# Potencia.net
KiCad netlist of a schematic drawn in Altium Designer
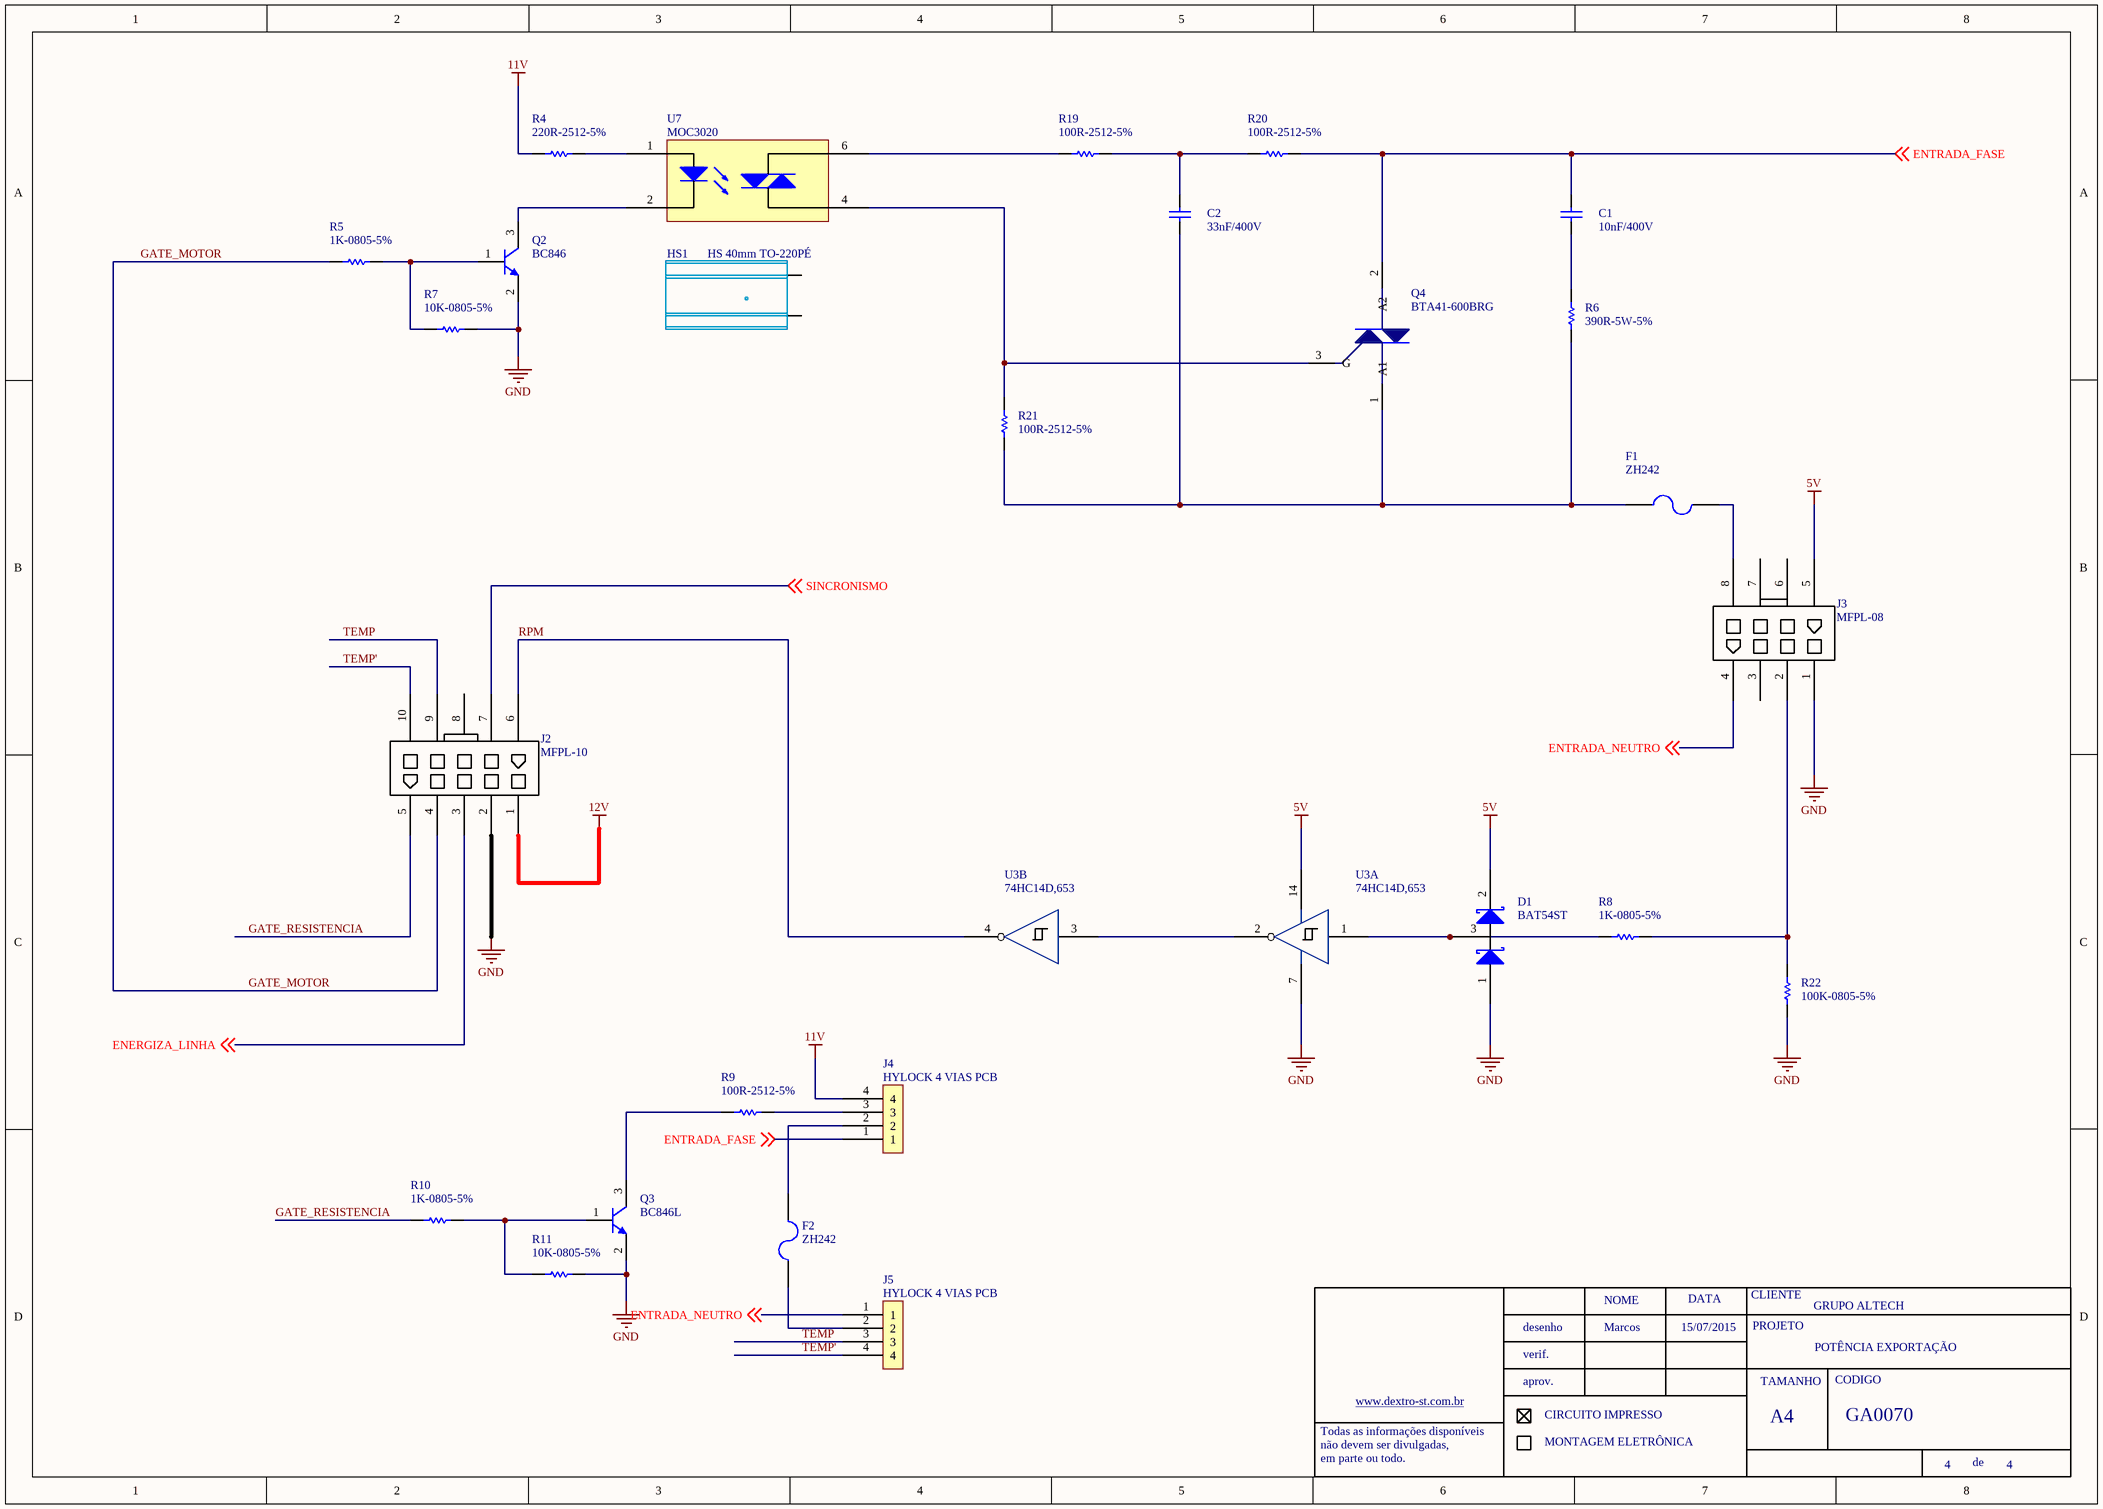
[diagram p0: Potencia.SchDoc]

(export (version "E")
  (design (tool "Eeschema 10.0.6"))
  (components
    (comp (ref "C1")
      (value "10nF/400V")
      (footprint "cap 330nF/250V")
      (description "100nF/50-0805-NPO")
      (libsource (lib "AquinoLib") (part "100nF/50-0805-NPO"))
    )
    (comp (ref "C2")
      (value "33nF/400V")
      (footprint "cap 330nF/250V")
      (description "100nF/50-0805-NPO")
      (libsource (lib "AquinoLib") (part "100nF/50-0805-NPO"))
    )
    (comp (ref "D1")
      (value "BAT54ST")
      (footprint "SOT23 - REVISADO ONDA")
      (libsource (lib "AquinoLib") (part "BAT54ST"))
    )
    (comp (ref "F1")
      (value "ZH242")
      (footprint "ZH242_REVISADO")
      (description "PORTA FUSÍVEL TIPO BERÇO")
      (libsource (lib "ChaveDigital3") (part "PORTA FUSÍVEL TIPO BERÇO"))
    )
    (comp (ref "F2")
      (value "ZH242")
      (footprint "ZH242_REVISADO")
      (description "PORTA FUSÍVEL TIPO BERÇO")
      (libsource (lib "ChaveDigital3") (part "PORTA FUSÍVEL TIPO BERÇO"))
    )
    (comp (ref "HS1")
      (value "HS 40mm TO-220PÉ")
      (footprint "dissipador grande")
      (libsource (lib "ChaveDigital3") (part "DISSIPADOR 40mm PÉ"))
    )
    (comp (ref "J2") (value "MFPL-10") (footprint "MFPC-10") (libsource (lib "AquinoLib") (part "MFPL-10")))
    (comp (ref "J3") (value "MFPL-08") (footprint "MFPC-08") (libsource (lib "AquinoLib") (part "MFPL-08")))
    (comp (ref "J4")
      (value "HYLOCK 4 VIAS PCB")
      (footprint "CONECTOR HYLOK 4 VIAS")
      (description "PCMC2-4")
      (libsource (lib "") (part "PCMC2-4_1"))
    )
    (comp (ref "J5")
      (value "HYLOCK 4 VIAS PCB")
      (footprint "CONECTOR HYLOK 4 VIAS")
      (description "PCMC2-4")
      (libsource (lib "AquinoLib") (part "PCMC2-4"))
    )
    (comp (ref "Q2")
      (value "BC846")
      (footprint "SOT23 - REVISADO ONDA")
      (description "BC846L")
      (libsource (lib "AquinoLib") (part "BC846"))
    )
    (comp (ref "Q3") (value "BC846L") (libsource (lib "AquinoLib") (part "BC846")))
    (comp (ref "Q4")
      (value "BTA41-600BRG")
      (footprint "TO-247 - duplicate")
      (libsource (lib "AquinoLib") (part "BTA41-600BRG"))
    )
    (comp (ref "R4")
      (value "220R-2512-5%")
      (footprint "2512 - REVISADO ONDA")
      (libsource (lib "AquinoLib") (part "220R-2512-5%"))
    )
    (comp (ref "R5")
      (value "1K-0805-5%")
      (footprint "0805-REVISADO ONDA")
      (description "10K-0805-5%")
      (libsource (lib "AquinoLib") (part "10K-0805-5%"))
    )
    (comp (ref "R6")
      (value "390R-5W-5%")
      (footprint "RESISTOR 5W FIO")
      (description "47R-5W-5%")
      (libsource (lib "AquinoLib") (part "47R-5W-5%"))
    )
    (comp (ref "R7")
      (value "10K-0805-5%")
      (footprint "0805-REVISADO ONDA")
      (libsource (lib "AquinoLib") (part "10K-0805-5%"))
    )
    (comp (ref "R8")
      (value "1K-0805-5%")
      (footprint "0805-REVISADO ONDA")
      (libsource (lib "AquinoLib") (part "1K-0805-5%"))
    )
    (comp (ref "R9")
      (value "100R-2512-5%")
      (footprint "2512 - REVISADO ONDA")
      (description "100R-0805-5%")
      (libsource (lib "AquinoLib") (part "100R-0805-5%"))
    )
    (comp (ref "R10")
      (value "1K-0805-5%")
      (footprint "0805-REVISADO ONDA")
      (libsource (lib "AquinoLib") (part "1K-0805-5%"))
    )
    (comp (ref "R11")
      (value "10K-0805-5%")
      (footprint "0805-REVISADO ONDA")
      (libsource (lib "AquinoLib") (part "10K-0805-5%"))
    )
    (comp (ref "R19")
      (value "100R-2512-5%")
      (footprint "2512 - REVISADO ONDA")
      (description "220R-2512-5%")
      (libsource (lib "AquinoLib") (part "220R-2512-5%"))
    )
    (comp (ref "R20")
      (value "100R-2512-5%")
      (footprint "2512 - REVISADO ONDA")
      (description "220R-2512-5%")
      (libsource (lib "AquinoLib") (part "220R-2512-5%"))
    )
    (comp (ref "R21")
      (value "100R-2512-5%")
      (footprint "2512 - REVISADO ONDA")
      (description "220R-2512-5%")
      (libsource (lib "AquinoLib") (part "220R-2512-5%"))
    )
    (comp (ref "R22")
      (value "100K-0805-5%")
      (footprint "0805-REVISADO ONDA")
      (libsource (lib "AquinoLib") (part "100K-0805-5%"))
    )
    (comp (ref "U3")
      (value "74HC14D,653")
      (footprint "SOIC 14 PINOS")
      (description "74HC14D")
      (libsource (lib "AquinoLib") (part "74HC14D"))
    )
    (comp (ref "U7") (value "MOC3020") (footprint "dip6") (libsource (lib "AquinoLib") (part "MOC3020")))
  )
  (nets
    (net (code "1") (name "/GATE_MOTOR") (class "Default")
      (node (ref "J2") (pin "4") (pinfunction "4_4") (pintype "passive"))
      (node (ref "R5") (pin "1") (pinfunction "1_1") (pintype "passive"))
    )
    (net (code "2") (name "/GATE_RESISTENCIA") (class "Default")
      (node (ref "J2") (pin "5") (pinfunction "5_5") (pintype "passive"))
      (node (ref "R10") (pin "1") (pinfunction "1_1") (pintype "passive"))
    )
    (net (code "3") (name "/RPM") (class "Default")
      (node (ref "J2") (pin "6") (pinfunction "6_6") (pintype "passive"))
      (node (ref "U3") (pin "4") (pinfunction "4_4") (pintype "passive"))
    )
    (net (code "4") (name "/TEMP") (class "Default")
      (node (ref "J2") (pin "9") (pinfunction "9_9") (pintype "passive"))
      (node (ref "J5") (pin "3") (pinfunction "3_3") (pintype "passive"))
    )
    (net (code "5") (name "/TEMP'") (class "Default")
      (node (ref "J2") (pin "10") (pinfunction "10_10") (pintype "passive"))
      (node (ref "J5") (pin "4") (pinfunction "4_4") (pintype "passive"))
    )
    (net (code "6") (name "5V") (class "Default")
      (node (ref "D1") (pin "2") (pinfunction "2_2") (pintype "passive"))
      (node (ref "J3") (pin "5") (pinfunction "5_5") (pintype "passive"))
      (node (ref "U3") (pin "14") (pinfunction "VCC_14") (pintype "passive"))
    )
    (net (code "7") (name "11V") (class "Default")
      (node (ref "J4") (pin "4") (pinfunction "4_4") (pintype "passive"))
      (node (ref "R4") (pin "2") (pinfunction "2_2") (pintype "passive"))
    )
    (net (code "8") (name "12V") (class "Default")
      (node (ref "J2") (pin "1") (pinfunction "1_1") (pintype "passive"))
    )
    (net (code "9") (name "ENERGIZA_LINHA") (class "Default")
      (node (ref "J2") (pin "3") (pinfunction "3_3") (pintype "passive"))
    )
    (net (code "10") (name "ENTRADA_FASE") (class "Default")
      (node (ref "C1") (pin "2") (pinfunction "2_2") (pintype "passive"))
      (node (ref "J4") (pin "1") (pinfunction "1_1") (pintype "passive"))
      (node (ref "Q4") (pin "2") (pinfunction "A2_2") (pintype "passive"))
      (node (ref "R20") (pin "2") (pinfunction "2_2") (pintype "passive"))
    )
    (net (code "11") (name "ENTRADA_NEUTRO") (class "Default")
      (node (ref "J3") (pin "4") (pinfunction "4_4") (pintype "passive"))
      (node (ref "J5") (pin "1") (pinfunction "1_1") (pintype "passive"))
    )
    (net (code "12") (name "GND") (class "Default")
      (node (ref "D1") (pin "1") (pinfunction "1_1") (pintype "passive"))
      (node (ref "J2") (pin "2") (pinfunction "2_2") (pintype "passive"))
      (node (ref "J3") (pin "1") (pinfunction "1_1") (pintype "passive"))
      (node (ref "Q2") (pin "2") (pinfunction "E_2") (pintype "passive"))
      (node (ref "Q3") (pin "2") (pinfunction "E_2") (pintype "passive"))
      (node (ref "R11") (pin "2") (pinfunction "2_2") (pintype "passive"))
      (node (ref "R22") (pin "1") (pinfunction "1_1") (pintype "passive"))
      (node (ref "R7") (pin "2") (pinfunction "2_2") (pintype "passive"))
      (node (ref "U3") (pin "7") (pinfunction "GND_7") (pintype "passive"))
    )
    (net (code "13") (name "Net-(C1-Pad1)") (class "Default")
      (node (ref "C1") (pin "1") (pinfunction "1_1") (pintype "passive"))
      (node (ref "R6") (pin "1") (pinfunction "1_1") (pintype "passive"))
    )
    (net (code "14") (name "Net-(C2-Pad2)") (class "Default")
      (node (ref "C2") (pin "2") (pinfunction "2_2") (pintype "passive"))
      (node (ref "R19") (pin "2") (pinfunction "2_2") (pintype "passive"))
      (node (ref "R20") (pin "1") (pinfunction "1_1") (pintype "passive"))
    )
    (net (code "15") (name "Net-(D1-Pad3)") (class "Default")
      (node (ref "D1") (pin "3") (pinfunction "3_3") (pintype "passive"))
      (node (ref "R8") (pin "1") (pinfunction "1_1") (pintype "passive"))
      (node (ref "U3") (pin "1") (pinfunction "1_1") (pintype "passive"))
    )
    (net (code "16") (name "Net-(F1-Pad1)") (class "Default")
      (node (ref "F1") (pin "1") (pinfunction "1_1") (pintype "passive"))
      (node (ref "J3") (pin "8") (pinfunction "8_8") (pintype "passive"))
    )
    (net (code "17") (name "Net-(F2-Pad1)") (class "Default")
      (node (ref "F2") (pin "1") (pinfunction "1_1") (pintype "passive"))
      (node (ref "J4") (pin "2") (pinfunction "2_2") (pintype "passive"))
    )
    (net (code "18") (name "Net-(F2-Pad2)") (class "Default")
      (node (ref "F2") (pin "2") (pinfunction "2_2") (pintype "passive"))
      (node (ref "J5") (pin "2") (pinfunction "2_2") (pintype "passive"))
    )
    (net (code "19") (name "Net-(J3-Pad2)") (class "Default")
      (node (ref "J3") (pin "2") (pinfunction "2_2") (pintype "passive"))
      (node (ref "R22") (pin "2") (pinfunction "2_2") (pintype "passive"))
      (node (ref "R8") (pin "2") (pinfunction "2_2") (pintype "passive"))
    )
    (net (code "20") (name "Net-(J4-Pad3)") (class "Default")
      (node (ref "J4") (pin "3") (pinfunction "3_3") (pintype "passive"))
      (node (ref "R9") (pin "2") (pinfunction "2_2") (pintype "passive"))
    )
    (net (code "21") (name "Net-(Q2-B)") (class "Default")
      (node (ref "Q2") (pin "1") (pinfunction "B_1") (pintype "passive"))
      (node (ref "R5") (pin "2") (pinfunction "2_2") (pintype "passive"))
      (node (ref "R7") (pin "1") (pinfunction "1_1") (pintype "passive"))
    )
    (net (code "22") (name "Net-(Q2-C)") (class "Default")
      (node (ref "Q2") (pin "3") (pinfunction "C_3") (pintype "passive"))
      (node (ref "U7") (pin "2") (pinfunction "2_2") (pintype "passive"))
    )
    (net (code "23") (name "Net-(Q3-B)") (class "Default")
      (node (ref "Q3") (pin "1") (pinfunction "B_1") (pintype "passive"))
      (node (ref "R10") (pin "2") (pinfunction "2_2") (pintype "passive"))
      (node (ref "R11") (pin "1") (pinfunction "1_1") (pintype "passive"))
    )
    (net (code "24") (name "Net-(Q3-C)") (class "Default")
      (node (ref "Q3") (pin "3") (pinfunction "C_3") (pintype "passive"))
      (node (ref "R9") (pin "1") (pinfunction "1_1") (pintype "passive"))
    )
    (net (code "25") (name "Net-(Q4-A1)") (class "Default")
      (node (ref "C2") (pin "1") (pinfunction "1_1") (pintype "passive"))
      (node (ref "F1") (pin "2") (pinfunction "2_2") (pintype "passive"))
      (node (ref "Q4") (pin "1") (pinfunction "A1_1") (pintype "passive"))
      (node (ref "R21") (pin "1") (pinfunction "1_1") (pintype "passive"))
      (node (ref "R6") (pin "2") (pinfunction "2_2") (pintype "passive"))
    )
    (net (code "26") (name "Net-(Q4-G)") (class "Default")
      (node (ref "Q4") (pin "3") (pinfunction "G_3") (pintype "passive"))
      (node (ref "R21") (pin "2") (pinfunction "2_2") (pintype "passive"))
      (node (ref "U7") (pin "4") (pinfunction "4_4") (pintype "passive"))
    )
    (net (code "27") (name "Net-(R4-Pad1)") (class "Default")
      (node (ref "R4") (pin "1") (pinfunction "1_1") (pintype "passive"))
      (node (ref "U7") (pin "1") (pinfunction "1_1") (pintype "passive"))
    )
    (net (code "28") (name "Net-(R19-Pad1)") (class "Default")
      (node (ref "R19") (pin "1") (pinfunction "1_1") (pintype "passive"))
      (node (ref "U7") (pin "6") (pinfunction "6_6") (pintype "passive"))
    )
    (net (code "29") (name "Net-(U3-Pad2)") (class "Default")
      (node (ref "U3") (pin "2") (pinfunction "2_2") (pintype "passive"))
      (node (ref "U3") (pin "3") (pinfunction "3_3") (pintype "passive"))
    )
    (net (code "30") (name "SINCRONISMO") (class "Default")
      (node (ref "J2") (pin "7") (pinfunction "7_7") (pintype "passive"))
    )
    (net (code "31") (name "unconnected-(HS1-Pad0)") (class "Default")
      (node (ref "HS1") (pin "0") (pinfunction "0_0") (pintype "passive"))
    )
    (net (code "32") (name "unconnected-(HS1-Pad1)") (class "Default")
      (node (ref "HS1") (pin "1") (pinfunction "1_1") (pintype "passive"))
    )
    (net (code "33") (name "unconnected-(J2-Pad8)") (class "Default")
      (node (ref "J2") (pin "8") (pinfunction "8_8") (pintype "passive"))
    )
    (net (code "34") (name "unconnected-(J3-Pad3)") (class "Default")
      (node (ref "J3") (pin "3") (pinfunction "3_3") (pintype "passive"))
    )
    (net (code "35") (name "unconnected-(J3-Pad6)") (class "Default")
      (node (ref "J3") (pin "6") (pinfunction "6_6") (pintype "passive"))
    )
    (net (code "36") (name "unconnected-(J3-Pad7)") (class "Default")
      (node (ref "J3") (pin "7") (pinfunction "7_7") (pintype "passive"))
    )
  )
)
